# HaHub.net
KiCad netlist of a schematic drawn in EAGLE
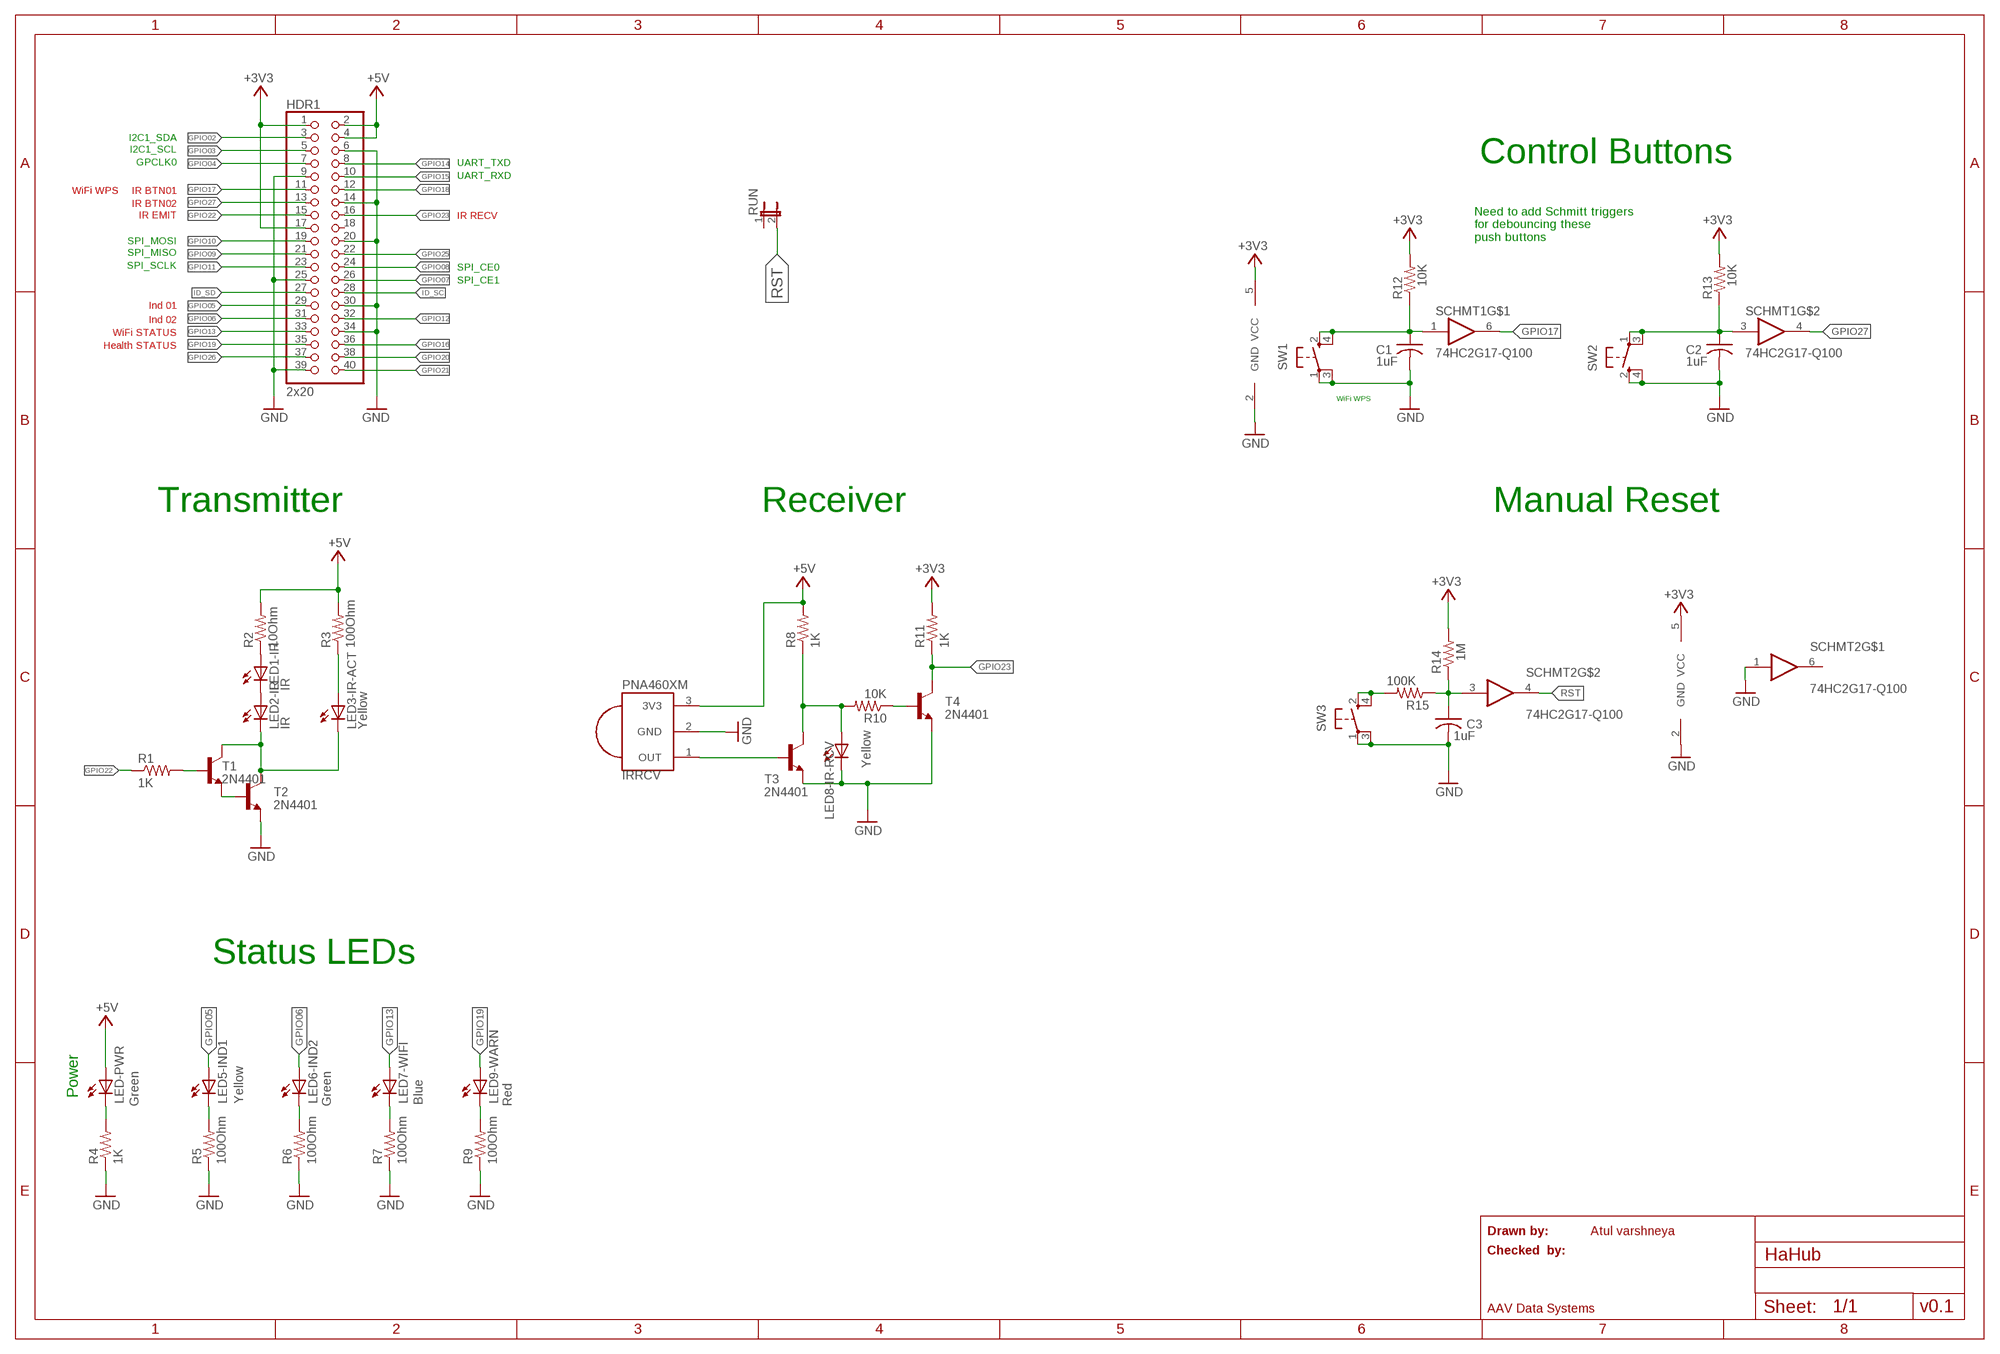
[diagram p0: schematic, sheet 1]

(export (version "E")
  (design (tool "Eeschema 10.0.6"))
  (components
    (comp (ref "C1")
      (value "1uF")
      (footprint "eagle-import:C0805")
      (fields (field (name "MPN") "MC0805B104K160CT"))
      (libsource (lib "eagle-import") (part "C-USC0805"))
    )
    (comp (ref "C2")
      (value "1uF")
      (footprint "eagle-import:C0805")
      (fields (field (name "MPN") "MC0805B104K160CT"))
      (libsource (lib "eagle-import") (part "C-USC0805"))
    )
    (comp (ref "C3")
      (value "1uF")
      (footprint "eagle-import:C0805")
      (fields (field (name "MPN") "MC0805B104K160CT"))
      (libsource (lib "eagle-import") (part "C-USC0805"))
    )
    (comp (ref "HDR1")
      (value "2x20")
      (footprint "eagle-import:2X20")
      (libsource (lib "eagle-import") (part "PINHD-2X20"))
    )
    (comp (ref "IRRCV")
      (value "PNA460XM")
      (footprint "eagle-import:PNA460XM")
      (fields (field (name "MPN") "TSOP38238"))
      (libsource (lib "eagle-import") (part "PNA460XM"))
    )
    (comp (ref "LED-PWR")
      (value "Green")
      (footprint "eagle-import:CHIPLED_0805")
      (fields (field (name "MPN") "150080GS75000"))
      (libsource (lib "eagle-import") (part "LEDCHIPLED_0805"))
    )
    (comp (ref "LED1-IR")
      (value "IR")
      (footprint "eagle-import:MICRO-SIDELED")
      (fields (field (name "MPN") "VSMB2943SLX01"))
      (libsource (lib "eagle-import") (part "LEDMICRO-SIDELED"))
    )
    (comp (ref "LED2-IR")
      (value "IR")
      (footprint "eagle-import:MICRO-SIDELED")
      (fields (field (name "MPN") "VSMB2943SLX01"))
      (libsource (lib "eagle-import") (part "LEDMICRO-SIDELED"))
    )
    (comp (ref "LED3-IR-ACT")
      (value "Yellow")
      (footprint "eagle-import:CHIPLED_0805")
      (fields (field (name "MPN") "150080YS75000"))
      (libsource (lib "eagle-import") (part "LEDCHIPLED_0805"))
    )
    (comp (ref "LED5-IND1")
      (value "Yellow")
      (footprint "eagle-import:CHIPLED_0805")
      (fields (field (name "MPN") "150080YS75000"))
      (libsource (lib "eagle-import") (part "LEDCHIPLED_0805"))
    )
    (comp (ref "LED6-IND2")
      (value "Green")
      (footprint "eagle-import:CHIPLED_0805")
      (fields (field (name "MPN") "150080GS75000"))
      (libsource (lib "eagle-import") (part "LEDCHIPLED_0805"))
    )
    (comp (ref "LED7-WIFI")
      (value "Blue")
      (footprint "eagle-import:CHIPLED_0805")
      (fields (field (name "MPN") "150080BS75000"))
      (libsource (lib "eagle-import") (part "LEDCHIPLED_0805"))
    )
    (comp (ref "LED8-IR-RCV")
      (value "Yellow")
      (footprint "eagle-import:CHIPLED_0805")
      (fields (field (name "MPN") "150080YS75000"))
      (libsource (lib "eagle-import") (part "LEDCHIPLED_0805"))
    )
    (comp (ref "LED9-WARN")
      (value "Red")
      (footprint "eagle-import:CHIPLED_0805")
      (fields (field (name "MPN") "150080RS75000"))
      (libsource (lib "eagle-import") (part "LEDCHIPLED_0805"))
    )
    (comp (ref "R1")
      (value "1K")
      (footprint "eagle-import:R0805")
      (fields (field (name "MF") "VISHAY/DALE") (field (name "MPN") "CRCW08051K00FKEA"))
      (libsource (lib "eagle-import") (part "R-US_R0805"))
    )
    (comp (ref "R2")
      (value "10Ohm")
      (footprint "eagle-import:R0805")
      (fields (field (name "MF") "VISHAY/DALE") (field (name "MPN") "CRCW080510R0FKEA"))
      (libsource (lib "eagle-import") (part "R-US_R0805"))
    )
    (comp (ref "R3")
      (value "100Ohm")
      (footprint "eagle-import:R0805")
      (fields (field (name "MF") "VISHAY/DALE") (field (name "MPN") "CRCW0805100RFKEA"))
      (libsource (lib "eagle-import") (part "R-US_R0805"))
    )
    (comp (ref "R4")
      (value "1K")
      (footprint "eagle-import:R0805")
      (fields (field (name "MF") "VISHAY/DALE") (field (name "MPN") "CRCW08051K00FKEA"))
      (libsource (lib "eagle-import") (part "R-US_R0805"))
    )
    (comp (ref "R5")
      (value "100Ohm")
      (footprint "eagle-import:R0805")
      (fields (field (name "MF") "VISHAY/DALE") (field (name "MPN") "CRCW0805100RFKEA"))
      (libsource (lib "eagle-import") (part "R-US_R0805"))
    )
    (comp (ref "R6")
      (value "100Ohm")
      (footprint "eagle-import:R0805")
      (fields (field (name "MF") "VISHAY/DALE") (field (name "MPN") "CRCW0805100RFKEA"))
      (libsource (lib "eagle-import") (part "R-US_R0805"))
    )
    (comp (ref "R7")
      (value "100Ohm")
      (footprint "eagle-import:R0805")
      (fields (field (name "MF") "VISHAY/DALE") (field (name "MPN") "CRCW0805100RFKEA"))
      (libsource (lib "eagle-import") (part "R-US_R0805"))
    )
    (comp (ref "R8")
      (value "1K")
      (footprint "eagle-import:R0805")
      (fields (field (name "MF") "VISHAY/DALE") (field (name "MPN") "CRCW08051K00FKEA"))
      (libsource (lib "eagle-import") (part "R-US_R0805"))
    )
    (comp (ref "R9")
      (value "100Ohm")
      (footprint "eagle-import:R0805")
      (fields (field (name "MF") "VISHAY/DALE") (field (name "MPN") "CRCW0805100RFKEA"))
      (libsource (lib "eagle-import") (part "R-US_R0805"))
    )
    (comp (ref "R10")
      (value "10K")
      (footprint "eagle-import:R0805")
      (fields (field (name "MF") "VISHAY/DALE") (field (name "MPN") "CRCW080510K0FKEA"))
      (libsource (lib "eagle-import") (part "R-US_R0805"))
    )
    (comp (ref "R11")
      (value "1K")
      (footprint "eagle-import:R0805")
      (fields (field (name "MF") "VISHAY/DALE") (field (name "MPN") "CRCW08051K00FKEA"))
      (libsource (lib "eagle-import") (part "R-US_R0805"))
    )
    (comp (ref "R12")
      (value "10K")
      (footprint "eagle-import:R0805")
      (fields (field (name "MF") "VISHAY/DALE") (field (name "MPN") "CRCW080510K0FKEA"))
      (libsource (lib "eagle-import") (part "R-US_R0805"))
    )
    (comp (ref "R13")
      (value "10K")
      (footprint "eagle-import:R0805")
      (fields (field (name "MF") "VISHAY/DALE") (field (name "MPN") "CRCW080510K0FKEA"))
      (libsource (lib "eagle-import") (part "R-US_R0805"))
    )
    (comp (ref "R14")
      (value "1M")
      (footprint "eagle-import:R0805")
      (fields (field (name "MF") "VISHAY/DALE") (field (name "MPN") "CRCW08051M00FKEA"))
      (libsource (lib "eagle-import") (part "R-US_R0805"))
    )
    (comp (ref "R15")
      (value "100K")
      (footprint "eagle-import:R0805")
      (fields (field (name "MF") "VISHAY/DALE") (field (name "MPN") "CRCW0805100KFKEA"))
      (libsource (lib "eagle-import") (part "R-US_R0805"))
    )
    (comp (ref "RUN")
      (value "RST")
      (footprint "eagle-import:JP1")
      (fields (field (name "MPN") "2211S-02G"))
      (libsource (lib "eagle-import") (part "JP1E"))
    )
    (comp (ref "SCHMT1")
      (value "74HC2G17-Q100")
      (footprint "eagle-import:SC-70-6L")
      (fields (field (name "MPN") "74HC2G17GW,125") (field (name "OC_NEWARK") "71R2196"))
      (libsource (lib "eagle-import") (part "74HC2G17-Q100"))
    )
    (comp (ref "SCHMT2")
      (value "74HC2G17-Q100")
      (footprint "eagle-import:SC-70-6L")
      (fields (field (name "MPN") "74HC2G17GW,125") (field (name "OC_NEWARK") "71R2196"))
      (libsource (lib "eagle-import") (part "74HC2G17-Q100"))
    )
    (comp (ref "SW1")
      (value "SPST_TACT-KMR2")
      (footprint "eagle-import:KMR2")
      (libsource (lib "eagle-import") (part "SPST_TACT-KMR2"))
    )
    (comp (ref "SW2")
      (value "SPST_TACT-KMR2")
      (footprint "eagle-import:KMR2")
      (libsource (lib "eagle-import") (part "SPST_TACT-KMR2"))
    )
    (comp (ref "SW3")
      (value "SPST_TACT-KMR2")
      (footprint "eagle-import:KMR2")
      (libsource (lib "eagle-import") (part "SPST_TACT-KMR2"))
    )
    (comp (ref "T1")
      (value "2N4401")
      (footprint "eagle-import:SOT23-BEC")
      (fields (field (name "MPN") "MMBT4401-TP"))
      (libsource (lib "eagle-import") (part "transistor-neu-to92_-NPN-SOT23-BECMMBT4401LT1"))
    )
    (comp (ref "T2")
      (value "2N4401")
      (footprint "eagle-import:SOT23-BEC")
      (fields (field (name "MPN") "MMBT4401-TP"))
      (libsource (lib "eagle-import") (part "transistor-neu-to92_-NPN-SOT23-BECMMBT4401LT1"))
    )
    (comp (ref "T3")
      (value "2N4401")
      (footprint "eagle-import:SOT23-BEC")
      (fields (field (name "MPN") "MMBT4401-TP"))
      (libsource (lib "eagle-import") (part "-NPN-SOT23-BECMMBT4401LT1"))
    )
    (comp (ref "T4")
      (value "2N4401")
      (footprint "eagle-import:SOT23-BEC")
      (fields (field (name "MPN") "MMBT4401-TP"))
      (libsource (lib "eagle-import") (part "-NPN-SOT23-BECMMBT4401LT1"))
    )
  )
  (nets
    (net (code "1") (name "+3V3") (class "Default")
      (node (ref "HDR1") (pin "1") (pinfunction "1_1") (pintype "passive"))
      (node (ref "HDR1") (pin "17") (pinfunction "17_17") (pintype "passive"))
      (node (ref "R11") (pin "2") (pinfunction "2_2") (pintype "passive"))
      (node (ref "R12") (pin "2") (pinfunction "2_2") (pintype "passive"))
      (node (ref "R13") (pin "2") (pinfunction "2_2") (pintype "passive"))
      (node (ref "R14") (pin "2") (pinfunction "2_2") (pintype "passive"))
      (node (ref "SCHMT1") (pin "5") (pinfunction "VCC_5") (pintype "bidirectional"))
      (node (ref "SCHMT2") (pin "5") (pinfunction "VCC_5") (pintype "bidirectional"))
    )
    (net (code "2") (name "+5V") (class "Default")
      (node (ref "HDR1") (pin "2") (pinfunction "2_2") (pintype "passive"))
      (node (ref "HDR1") (pin "4") (pinfunction "4_4") (pintype "passive"))
      (node (ref "IRRCV") (pin "3") (pinfunction "3V3_3") (pintype "power_in"))
      (node (ref "LED-PWR") (pin "A") (pinfunction "A_A") (pintype "passive"))
      (node (ref "R2") (pin "2") (pinfunction "2_2") (pintype "passive"))
      (node (ref "R3") (pin "2") (pinfunction "2_2") (pintype "passive"))
      (node (ref "R8") (pin "2") (pinfunction "2_2") (pintype "passive"))
    )
    (net (code "3") (name "GND") (class "Default")
      (node (ref "C1") (pin "2") (pinfunction "2_2") (pintype "passive"))
      (node (ref "C2") (pin "2") (pinfunction "2_2") (pintype "passive"))
      (node (ref "C3") (pin "2") (pinfunction "2_2") (pintype "passive"))
      (node (ref "HDR1") (pin "14") (pinfunction "14_14") (pintype "passive"))
      (node (ref "HDR1") (pin "20") (pinfunction "20_20") (pintype "passive"))
      (node (ref "HDR1") (pin "25") (pinfunction "25_25") (pintype "passive"))
      (node (ref "HDR1") (pin "30") (pinfunction "30_30") (pintype "passive"))
      (node (ref "HDR1") (pin "34") (pinfunction "34_34") (pintype "passive"))
      (node (ref "HDR1") (pin "39") (pinfunction "39_39") (pintype "passive"))
      (node (ref "HDR1") (pin "6") (pinfunction "6_6") (pintype "passive"))
      (node (ref "HDR1") (pin "9") (pinfunction "9_9") (pintype "passive"))
      (node (ref "IRRCV") (pin "2") (pinfunction "GND_2") (pintype "power_in"))
      (node (ref "LED8-IR-RCV") (pin "C") (pinfunction "C_C") (pintype "passive"))
      (node (ref "R4") (pin "1") (pinfunction "1_1") (pintype "passive"))
      (node (ref "R5") (pin "1") (pinfunction "1_1") (pintype "passive"))
      (node (ref "R6") (pin "1") (pinfunction "1_1") (pintype "passive"))
      (node (ref "R7") (pin "1") (pinfunction "1_1") (pintype "passive"))
      (node (ref "R9") (pin "1") (pinfunction "1_1") (pintype "passive"))
      (node (ref "SCHMT1") (pin "2") (pinfunction "GND_2") (pintype "bidirectional"))
      (node (ref "SCHMT2") (pin "1") (pinfunction "I_1") (pintype "input"))
      (node (ref "SCHMT2") (pin "2") (pinfunction "GND_2") (pintype "bidirectional"))
      (node (ref "SW1") (pin "1") (pinfunction "P_1") (pintype "passive"))
      (node (ref "SW1") (pin "3") (pinfunction "P1_3") (pintype "passive"))
      (node (ref "SW2") (pin "2") (pinfunction "S_2") (pintype "passive"))
      (node (ref "SW2") (pin "4") (pinfunction "S1_4") (pintype "passive"))
      (node (ref "SW3") (pin "1") (pinfunction "P_1") (pintype "passive"))
      (node (ref "SW3") (pin "3") (pinfunction "P1_3") (pintype "passive"))
      (node (ref "T2") (pin "E") (pinfunction "E_E") (pintype "passive"))
      (node (ref "T3") (pin "E") (pinfunction "E_E") (pintype "passive"))
      (node (ref "T4") (pin "E") (pinfunction "E_E") (pintype "passive"))
    )
    (net (code "4") (name "GPIO02") (class "Default")
      (node (ref "HDR1") (pin "3") (pinfunction "3_3") (pintype "passive"))
    )
    (net (code "5") (name "GPIO03") (class "Default")
      (node (ref "HDR1") (pin "5") (pinfunction "5_5") (pintype "passive"))
    )
    (net (code "6") (name "GPIO04") (class "Default")
      (node (ref "HDR1") (pin "7") (pinfunction "7_7") (pintype "passive"))
    )
    (net (code "7") (name "GPIO05") (class "Default")
      (node (ref "HDR1") (pin "29") (pinfunction "29_29") (pintype "passive"))
      (node (ref "LED5-IND1") (pin "A") (pinfunction "A_A") (pintype "passive"))
    )
    (net (code "8") (name "GPIO06") (class "Default")
      (node (ref "HDR1") (pin "31") (pinfunction "31_31") (pintype "passive"))
      (node (ref "LED6-IND2") (pin "A") (pinfunction "A_A") (pintype "passive"))
    )
    (net (code "9") (name "GPIO07") (class "Default")
      (node (ref "HDR1") (pin "26") (pinfunction "26_26") (pintype "passive"))
    )
    (net (code "10") (name "GPIO08") (class "Default")
      (node (ref "HDR1") (pin "24") (pinfunction "24_24") (pintype "passive"))
    )
    (net (code "11") (name "GPIO09") (class "Default")
      (node (ref "HDR1") (pin "21") (pinfunction "21_21") (pintype "passive"))
    )
    (net (code "12") (name "GPIO10") (class "Default")
      (node (ref "HDR1") (pin "19") (pinfunction "19_19") (pintype "passive"))
    )
    (net (code "13") (name "GPIO11") (class "Default")
      (node (ref "HDR1") (pin "23") (pinfunction "23_23") (pintype "passive"))
    )
    (net (code "14") (name "GPIO12") (class "Default")
      (node (ref "HDR1") (pin "32") (pinfunction "32_32") (pintype "passive"))
    )
    (net (code "15") (name "GPIO13") (class "Default")
      (node (ref "HDR1") (pin "33") (pinfunction "33_33") (pintype "passive"))
      (node (ref "LED7-WIFI") (pin "A") (pinfunction "A_A") (pintype "passive"))
    )
    (net (code "16") (name "GPIO14") (class "Default")
      (node (ref "HDR1") (pin "8") (pinfunction "8_8") (pintype "passive"))
    )
    (net (code "17") (name "GPIO15") (class "Default")
      (node (ref "HDR1") (pin "10") (pinfunction "10_10") (pintype "passive"))
    )
    (net (code "18") (name "GPIO16") (class "Default")
      (node (ref "HDR1") (pin "36") (pinfunction "36_36") (pintype "passive"))
    )
    (net (code "19") (name "GPIO17") (class "Default")
      (node (ref "HDR1") (pin "11") (pinfunction "11_11") (pintype "passive"))
      (node (ref "SCHMT1") (pin "6") (pinfunction "O_6") (pintype "output"))
    )
    (net (code "20") (name "GPIO18") (class "Default")
      (node (ref "HDR1") (pin "12") (pinfunction "12_12") (pintype "passive"))
    )
    (net (code "21") (name "GPIO19") (class "Default")
      (node (ref "HDR1") (pin "35") (pinfunction "35_35") (pintype "passive"))
      (node (ref "LED9-WARN") (pin "A") (pinfunction "A_A") (pintype "passive"))
    )
    (net (code "22") (name "GPIO20") (class "Default")
      (node (ref "HDR1") (pin "38") (pinfunction "38_38") (pintype "passive"))
    )
    (net (code "23") (name "GPIO21") (class "Default")
      (node (ref "HDR1") (pin "40") (pinfunction "40_40") (pintype "passive"))
    )
    (net (code "24") (name "GPIO22") (class "Default")
      (node (ref "HDR1") (pin "15") (pinfunction "15_15") (pintype "passive"))
      (node (ref "R1") (pin "1") (pinfunction "1_1") (pintype "passive"))
    )
    (net (code "25") (name "GPIO23") (class "Default")
      (node (ref "HDR1") (pin "16") (pinfunction "16_16") (pintype "passive"))
      (node (ref "R11") (pin "1") (pinfunction "1_1") (pintype "passive"))
      (node (ref "T4") (pin "C") (pinfunction "C_C") (pintype "passive"))
    )
    (net (code "26") (name "GPIO25") (class "Default")
      (node (ref "HDR1") (pin "22") (pinfunction "22_22") (pintype "passive"))
    )
    (net (code "27") (name "GPIO26") (class "Default")
      (node (ref "HDR1") (pin "37") (pinfunction "37_37") (pintype "passive"))
    )
    (net (code "28") (name "GPIO27") (class "Default")
      (node (ref "HDR1") (pin "13") (pinfunction "13_13") (pintype "passive"))
      (node (ref "SCHMT1") (pin "4") (pinfunction "O_4") (pintype "output"))
    )
    (net (code "29") (name "ID_SC") (class "Default")
      (node (ref "HDR1") (pin "28") (pinfunction "28_28") (pintype "passive"))
    )
    (net (code "30") (name "ID_SD") (class "Default")
      (node (ref "HDR1") (pin "27") (pinfunction "27_27") (pintype "passive"))
    )
    (net (code "31") (name "Net-(IRRCV-OUT)") (class "Default")
      (node (ref "IRRCV") (pin "1") (pinfunction "OUT_1") (pintype "output"))
      (node (ref "T3") (pin "B") (pinfunction "B_B") (pintype "passive"))
    )
    (net (code "32") (name "Net-(LED-PWR-PadC)") (class "Default")
      (node (ref "LED-PWR") (pin "C") (pinfunction "C_C") (pintype "passive"))
      (node (ref "R4") (pin "2") (pinfunction "2_2") (pintype "passive"))
    )
    (net (code "33") (name "Net-(LED1-IR-PadA)") (class "Default")
      (node (ref "LED1-IR") (pin "A") (pinfunction "A_A") (pintype "passive"))
      (node (ref "R2") (pin "1") (pinfunction "1_1") (pintype "passive"))
    )
    (net (code "34") (name "Net-(LED1-IR-PadC)") (class "Default")
      (node (ref "LED1-IR") (pin "C") (pinfunction "C_C") (pintype "passive"))
      (node (ref "LED2-IR") (pin "A") (pinfunction "A_A") (pintype "passive"))
    )
    (net (code "35") (name "Net-(LED2-IR-PadC)") (class "Default")
      (node (ref "LED2-IR") (pin "C") (pinfunction "C_C") (pintype "passive"))
      (node (ref "LED3-IR-ACT") (pin "C") (pinfunction "C_C") (pintype "passive"))
      (node (ref "T1") (pin "C") (pinfunction "C_C") (pintype "passive"))
      (node (ref "T2") (pin "C") (pinfunction "C_C") (pintype "passive"))
    )
    (net (code "36") (name "Net-(LED3-IR-ACT-PadA)") (class "Default")
      (node (ref "LED3-IR-ACT") (pin "A") (pinfunction "A_A") (pintype "passive"))
      (node (ref "R3") (pin "1") (pinfunction "1_1") (pintype "passive"))
    )
    (net (code "37") (name "Net-(LED5-IND1-PadC)") (class "Default")
      (node (ref "LED5-IND1") (pin "C") (pinfunction "C_C") (pintype "passive"))
      (node (ref "R5") (pin "2") (pinfunction "2_2") (pintype "passive"))
    )
    (net (code "38") (name "Net-(LED6-IND2-PadC)") (class "Default")
      (node (ref "LED6-IND2") (pin "C") (pinfunction "C_C") (pintype "passive"))
      (node (ref "R6") (pin "2") (pinfunction "2_2") (pintype "passive"))
    )
    (net (code "39") (name "Net-(LED7-WIFI-PadC)") (class "Default")
      (node (ref "LED7-WIFI") (pin "C") (pinfunction "C_C") (pintype "passive"))
      (node (ref "R7") (pin "2") (pinfunction "2_2") (pintype "passive"))
    )
    (net (code "40") (name "Net-(LED8-IR-RCV-PadA)") (class "Default")
      (node (ref "LED8-IR-RCV") (pin "A") (pinfunction "A_A") (pintype "passive"))
      (node (ref "R10") (pin "2") (pinfunction "2_2") (pintype "passive"))
      (node (ref "R8") (pin "1") (pinfunction "1_1") (pintype "passive"))
      (node (ref "T3") (pin "C") (pinfunction "C_C") (pintype "passive"))
    )
    (net (code "41") (name "Net-(LED9-WARN-PadC)") (class "Default")
      (node (ref "LED9-WARN") (pin "C") (pinfunction "C_C") (pintype "passive"))
      (node (ref "R9") (pin "2") (pinfunction "2_2") (pintype "passive"))
    )
    (net (code "42") (name "Net-(R1-Pad2)") (class "Default")
      (node (ref "R1") (pin "2") (pinfunction "2_2") (pintype "passive"))
      (node (ref "T1") (pin "B") (pinfunction "B_B") (pintype "passive"))
    )
    (net (code "43") (name "Net-(R10-Pad1)") (class "Default")
      (node (ref "R10") (pin "1") (pinfunction "1_1") (pintype "passive"))
      (node (ref "T4") (pin "B") (pinfunction "B_B") (pintype "passive"))
    )
    (net (code "44") (name "Net-(SCHMT1A-I)") (class "Default")
      (node (ref "C1") (pin "1") (pinfunction "1_1") (pintype "passive"))
      (node (ref "R12") (pin "1") (pinfunction "1_1") (pintype "passive"))
      (node (ref "SCHMT1") (pin "1") (pinfunction "I_1") (pintype "input"))
      (node (ref "SW1") (pin "2") (pinfunction "S_2") (pintype "passive"))
      (node (ref "SW1") (pin "4") (pinfunction "S1_4") (pintype "passive"))
    )
    (net (code "45") (name "Net-(SCHMT1B-I)") (class "Default")
      (node (ref "C2") (pin "1") (pinfunction "1_1") (pintype "passive"))
      (node (ref "R13") (pin "1") (pinfunction "1_1") (pintype "passive"))
      (node (ref "SCHMT1") (pin "3") (pinfunction "I_3") (pintype "input"))
      (node (ref "SW2") (pin "1") (pinfunction "P_1") (pintype "passive"))
      (node (ref "SW2") (pin "3") (pinfunction "P1_3") (pintype "passive"))
    )
    (net (code "46") (name "Net-(SCHMT2B-I)") (class "Default")
      (node (ref "C3") (pin "1") (pinfunction "1_1") (pintype "passive"))
      (node (ref "R14") (pin "1") (pinfunction "1_1") (pintype "passive"))
      (node (ref "R15") (pin "1") (pinfunction "1_1") (pintype "passive"))
      (node (ref "SCHMT2") (pin "3") (pinfunction "I_3") (pintype "input"))
    )
    (net (code "47") (name "Net-(SW3-S)") (class "Default")
      (node (ref "R15") (pin "2") (pinfunction "2_2") (pintype "passive"))
      (node (ref "SW3") (pin "2") (pinfunction "S_2") (pintype "passive"))
      (node (ref "SW3") (pin "4") (pinfunction "S1_4") (pintype "passive"))
    )
    (net (code "48") (name "Net-(T1-PadE)") (class "Default")
      (node (ref "T1") (pin "E") (pinfunction "E_E") (pintype "passive"))
      (node (ref "T2") (pin "B") (pinfunction "B_B") (pintype "passive"))
    )
    (net (code "49") (name "RST") (class "Default")
      (node (ref "RUN") (pin "2") (pinfunction "2_2") (pintype "passive"))
      (node (ref "SCHMT2") (pin "4") (pinfunction "O_4") (pintype "output"))
    )
    (net (code "50") (name "unconnected-(HDR1-Pad18)") (class "Default")
      (node (ref "HDR1") (pin "18") (pinfunction "18_18") (pintype "passive"))
    )
    (net (code "51") (name "unconnected-(RUN-Pad1)") (class "Default")
      (node (ref "RUN") (pin "1") (pinfunction "1_1") (pintype "passive"))
    )
    (net (code "52") (name "unconnected-(SCHMT2A-O-Pad6)") (class "Default")
      (node (ref "SCHMT2") (pin "6") (pinfunction "O_6") (pintype "output"))
    )
  )
)
